# M103.net
KiCad netlist of a schematic drawn in EAGLE
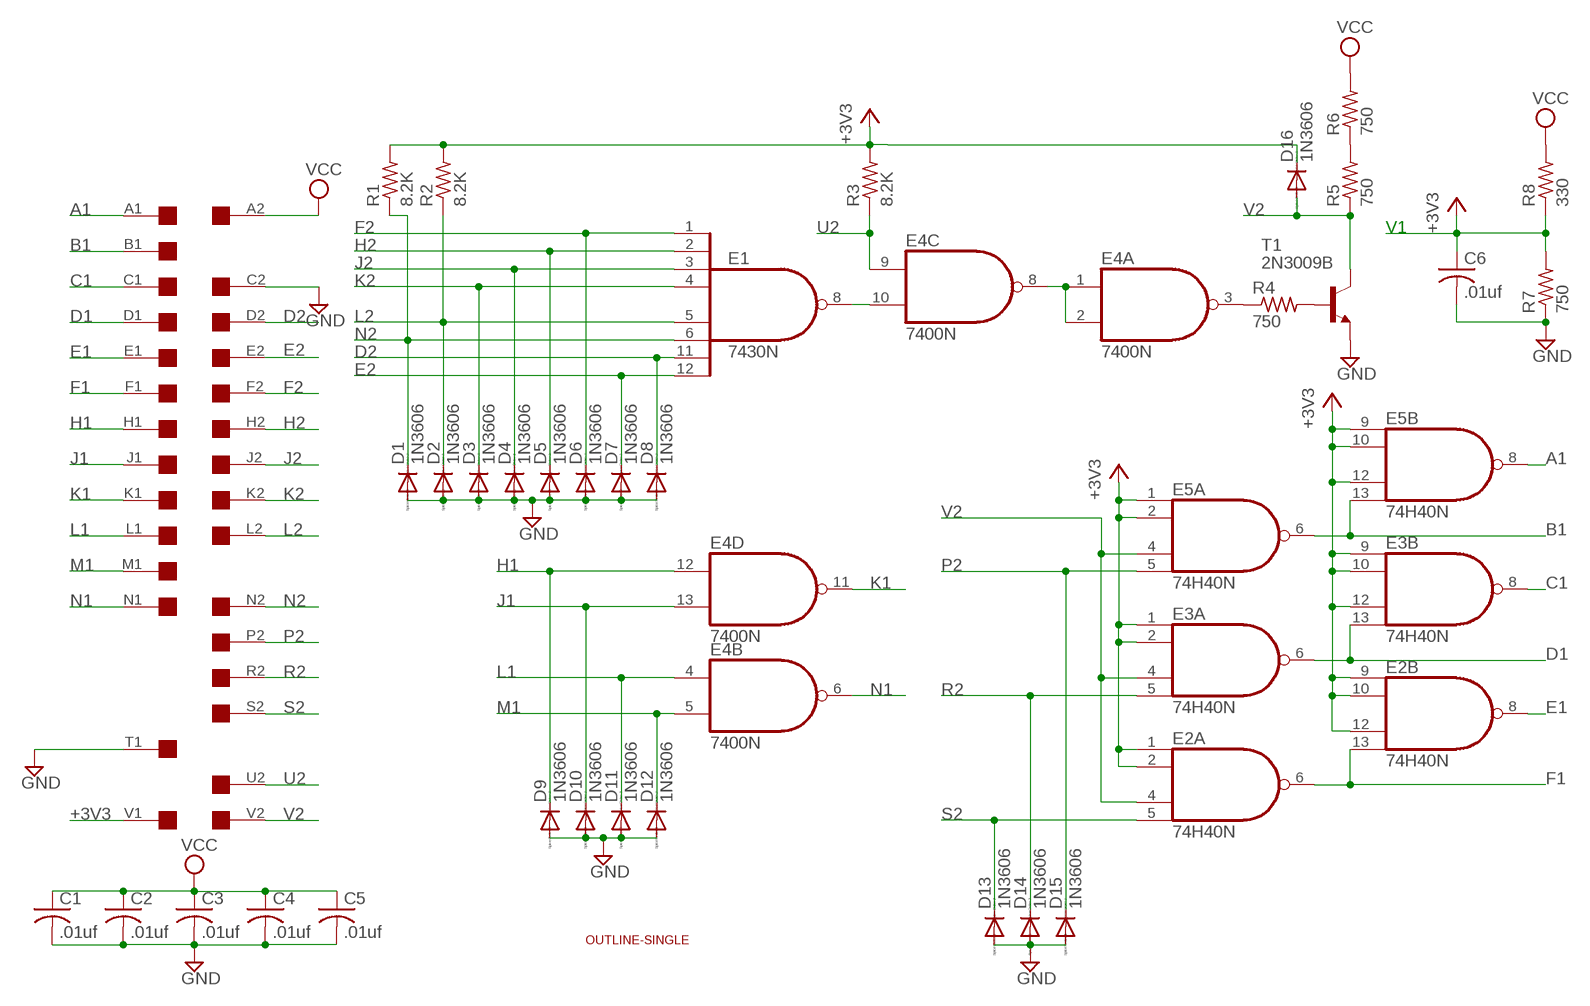
[diagram p0: schematic, sheet 1]

(export (version "E")
  (design (tool "Eeschema 10.0.6"))
  (components
    (comp (ref "C1")
      (value ".01uf")
      (footprint "eagle-import:C050-025X075")
      (libsource (lib "eagle-import") (part "C-US050-025X075"))
    )
    (comp (ref "C2")
      (value ".01uf")
      (footprint "eagle-import:C050-025X075")
      (libsource (lib "eagle-import") (part "C-US050-025X075"))
    )
    (comp (ref "C3")
      (value ".01uf")
      (footprint "eagle-import:C050-025X075")
      (libsource (lib "eagle-import") (part "C-US050-025X075"))
    )
    (comp (ref "C4")
      (value ".01uf")
      (footprint "eagle-import:C050-025X075")
      (libsource (lib "eagle-import") (part "C-US050-025X075"))
    )
    (comp (ref "C5")
      (value ".01uf")
      (footprint "eagle-import:C050-025X075")
      (libsource (lib "eagle-import") (part "C-US050-025X075"))
    )
    (comp (ref "C6")
      (value ".01uf")
      (footprint "eagle-import:C050-025X075")
      (libsource (lib "eagle-import") (part "C-US050-025X075"))
    )
    (comp (ref "D1")
      (value "1N3606")
      (footprint "eagle-import:DO35-10")
      (libsource (lib "eagle-import") (part "1N4148DO35-10"))
    )
    (comp (ref "D2")
      (value "1N3606")
      (footprint "eagle-import:DO35-10")
      (libsource (lib "eagle-import") (part "1N4148DO35-10"))
    )
    (comp (ref "D3")
      (value "1N3606")
      (footprint "eagle-import:DO35-10")
      (libsource (lib "eagle-import") (part "1N4148DO35-10"))
    )
    (comp (ref "D4")
      (value "1N3606")
      (footprint "eagle-import:DO35-10")
      (libsource (lib "eagle-import") (part "1N4148DO35-10"))
    )
    (comp (ref "D5")
      (value "1N3606")
      (footprint "eagle-import:DO35-10")
      (libsource (lib "eagle-import") (part "1N4148DO35-10"))
    )
    (comp (ref "D6")
      (value "1N3606")
      (footprint "eagle-import:DO35-10")
      (libsource (lib "eagle-import") (part "1N4148DO35-10"))
    )
    (comp (ref "D7")
      (value "1N3606")
      (footprint "eagle-import:DO35-10")
      (libsource (lib "eagle-import") (part "1N4148DO35-10"))
    )
    (comp (ref "D8")
      (value "1N3606")
      (footprint "eagle-import:DO35-10")
      (libsource (lib "eagle-import") (part "1N4148DO35-10"))
    )
    (comp (ref "D9")
      (value "1N3606")
      (footprint "eagle-import:DO35-10")
      (libsource (lib "eagle-import") (part "1N4148DO35-10"))
    )
    (comp (ref "D10")
      (value "1N3606")
      (footprint "eagle-import:DO35-10")
      (libsource (lib "eagle-import") (part "1N4148DO35-10"))
    )
    (comp (ref "D11")
      (value "1N3606")
      (footprint "eagle-import:DO35-10")
      (libsource (lib "eagle-import") (part "1N4148DO35-10"))
    )
    (comp (ref "D12")
      (value "1N3606")
      (footprint "eagle-import:DO35-10")
      (libsource (lib "eagle-import") (part "1N4148DO35-10"))
    )
    (comp (ref "D13")
      (value "1N3606")
      (footprint "eagle-import:DO35-10")
      (libsource (lib "eagle-import") (part "1N4148DO35-10"))
    )
    (comp (ref "D14")
      (value "1N3606")
      (footprint "eagle-import:DO35-10")
      (libsource (lib "eagle-import") (part "1N4148DO35-10"))
    )
    (comp (ref "D15")
      (value "1N3606")
      (footprint "eagle-import:DO35-10")
      (libsource (lib "eagle-import") (part "1N4148DO35-10"))
    )
    (comp (ref "D16")
      (value "1N3606")
      (footprint "eagle-import:DO35-10")
      (libsource (lib "eagle-import") (part "1N4148DO35-10"))
    )
    (comp (ref "E1")
      (value "7430N")
      (footprint "eagle-import:DIL14")
      (libsource (lib "eagle-import") (part "7430N"))
    )
    (comp (ref "E2")
      (value "74H40N")
      (footprint "eagle-import:DIL14")
      (libsource (lib "eagle-import") (part "7420NS"))
    )
    (comp (ref "E3")
      (value "74H40N")
      (footprint "eagle-import:DIL14")
      (libsource (lib "eagle-import") (part "7420NS"))
    )
    (comp (ref "E4")
      (value "7400N")
      (footprint "eagle-import:DIL14")
      (libsource (lib "eagle-import") (part "7400N"))
    )
    (comp (ref "E5")
      (value "74H40N")
      (footprint "eagle-import:DIL14")
      (libsource (lib "eagle-import") (part "7420NS"))
    )
    (comp (ref "R1")
      (value "8.2K")
      (footprint "eagle-import:0207_10")
      (libsource (lib "eagle-import") (part "R-US_0207/10"))
    )
    (comp (ref "R2")
      (value "8.2K")
      (footprint "eagle-import:0207_10")
      (libsource (lib "eagle-import") (part "R-US_0207/10"))
    )
    (comp (ref "R3")
      (value "8.2K")
      (footprint "eagle-import:0207_10")
      (libsource (lib "eagle-import") (part "R-US_0207/10"))
    )
    (comp (ref "R4")
      (value "750")
      (footprint "eagle-import:0207_10")
      (libsource (lib "eagle-import") (part "R-US_0207/10"))
    )
    (comp (ref "R5")
      (value "750")
      (footprint "eagle-import:0207_10")
      (libsource (lib "eagle-import") (part "R-US_0207/10"))
    )
    (comp (ref "R6")
      (value "750")
      (footprint "eagle-import:0207_10")
      (libsource (lib "eagle-import") (part "R-US_0207/10"))
    )
    (comp (ref "R7")
      (value "750")
      (footprint "eagle-import:0207_10")
      (libsource (lib "eagle-import") (part "R-US_0207/10"))
    )
    (comp (ref "R8")
      (value "330")
      (footprint "eagle-import:0207_10")
      (libsource (lib "eagle-import") (part "R-US_0207/10"))
    )
    (comp (ref "T1")
      (value "2N3009B")
      (footprint "eagle-import:TO39")
      (libsource (lib "eagle-import") (part "-NPN-TO39-EBC2N1613"))
    )
    (comp (ref "U$8")
      (value "SINGLE")
      (footprint "eagle-import:EDGE-CON2")
      (libsource (lib "eagle-import") (part "SINGLE"))
    )
    (comp (ref "U$9")
      (value "OUTLINE-SINGLE")
      (footprint "eagle-import:SINGLE")
      (libsource (lib "eagle-import") (part "OUTLINE-SINGLE"))
    )
  )
  (nets
    (net (code "1") (name "+3V3") (class "Default")
      (node (ref "C6") (pin "1") (pinfunction "1_1") (pintype "passive"))
      (node (ref "D16") (pin "C") (pinfunction "C_C") (pintype "passive"))
      (node (ref "E2") (pin "1") (pinfunction "I0_1") (pintype "input"))
      (node (ref "E2") (pin "10") (pinfunction "I1_10") (pintype "input"))
      (node (ref "E2") (pin "12") (pinfunction "I2_12") (pintype "input"))
      (node (ref "E2") (pin "2") (pinfunction "I1_2") (pintype "input"))
      (node (ref "E2") (pin "9") (pinfunction "I0_9") (pintype "input"))
      (node (ref "E3") (pin "1") (pinfunction "I0_1") (pintype "input"))
      (node (ref "E3") (pin "10") (pinfunction "I1_10") (pintype "input"))
      (node (ref "E3") (pin "12") (pinfunction "I2_12") (pintype "input"))
      (node (ref "E3") (pin "2") (pinfunction "I1_2") (pintype "input"))
      (node (ref "E3") (pin "9") (pinfunction "I0_9") (pintype "input"))
      (node (ref "E5") (pin "1") (pinfunction "I0_1") (pintype "input"))
      (node (ref "E5") (pin "10") (pinfunction "I1_10") (pintype "input"))
      (node (ref "E5") (pin "12") (pinfunction "I2_12") (pintype "input"))
      (node (ref "E5") (pin "2") (pinfunction "I1_2") (pintype "input"))
      (node (ref "E5") (pin "9") (pinfunction "I0_9") (pintype "input"))
      (node (ref "R1") (pin "2") (pinfunction "2_2") (pintype "passive"))
      (node (ref "R2") (pin "2") (pinfunction "2_2") (pintype "passive"))
      (node (ref "R3") (pin "2") (pinfunction "2_2") (pintype "passive"))
      (node (ref "R7") (pin "2") (pinfunction "2_2") (pintype "passive"))
      (node (ref "R8") (pin "1") (pinfunction "1_1") (pintype "passive"))
      (node (ref "U$8") (pin "V1") (pinfunction "1_V1") (pintype "bidirectional"))
    )
    (net (code "2") (name "/A1") (class "Default")
      (node (ref "E5") (pin "8") (pinfunction "O_8") (pintype "output"))
      (node (ref "U$8") (pin "A1") (pinfunction "1_A1") (pintype "bidirectional"))
    )
    (net (code "3") (name "/B1") (class "Default")
      (node (ref "E5") (pin "13") (pinfunction "I3_13") (pintype "input"))
      (node (ref "E5") (pin "6") (pinfunction "O_6") (pintype "output"))
      (node (ref "U$8") (pin "B1") (pinfunction "1_B1") (pintype "bidirectional"))
    )
    (net (code "4") (name "/C1") (class "Default")
      (node (ref "E3") (pin "8") (pinfunction "O_8") (pintype "output"))
      (node (ref "U$8") (pin "C1") (pinfunction "1_C1") (pintype "bidirectional"))
    )
    (net (code "5") (name "/D1") (class "Default")
      (node (ref "E3") (pin "13") (pinfunction "I3_13") (pintype "input"))
      (node (ref "E3") (pin "6") (pinfunction "O_6") (pintype "output"))
      (node (ref "U$8") (pin "D1") (pinfunction "1_D1") (pintype "bidirectional"))
    )
    (net (code "6") (name "/D2") (class "Default")
      (node (ref "D8") (pin "C") (pinfunction "C_C") (pintype "passive"))
      (node (ref "E1") (pin "11") (pinfunction "I6_11") (pintype "input"))
      (node (ref "U$8") (pin "D2") (pinfunction "1_D2") (pintype "bidirectional"))
    )
    (net (code "7") (name "/E1") (class "Default")
      (node (ref "E2") (pin "8") (pinfunction "O_8") (pintype "output"))
      (node (ref "U$8") (pin "E1") (pinfunction "1_E1") (pintype "bidirectional"))
    )
    (net (code "8") (name "/E2") (class "Default")
      (node (ref "D7") (pin "C") (pinfunction "C_C") (pintype "passive"))
      (node (ref "E1") (pin "12") (pinfunction "I7_12") (pintype "input"))
      (node (ref "U$8") (pin "E2") (pinfunction "1_E2") (pintype "bidirectional"))
    )
    (net (code "9") (name "/F1") (class "Default")
      (node (ref "E2") (pin "13") (pinfunction "I3_13") (pintype "input"))
      (node (ref "E2") (pin "6") (pinfunction "O_6") (pintype "output"))
      (node (ref "U$8") (pin "F1") (pinfunction "1_F1") (pintype "bidirectional"))
    )
    (net (code "10") (name "/F2") (class "Default")
      (node (ref "D6") (pin "C") (pinfunction "C_C") (pintype "passive"))
      (node (ref "E1") (pin "1") (pinfunction "I0_1") (pintype "input"))
      (node (ref "U$8") (pin "F2") (pinfunction "1_F2") (pintype "bidirectional"))
    )
    (net (code "11") (name "/H1") (class "Default")
      (node (ref "D9") (pin "C") (pinfunction "C_C") (pintype "passive"))
      (node (ref "E4") (pin "12") (pinfunction "I0_12") (pintype "input"))
      (node (ref "U$8") (pin "H1") (pinfunction "1_H1") (pintype "bidirectional"))
    )
    (net (code "12") (name "/H2") (class "Default")
      (node (ref "D5") (pin "C") (pinfunction "C_C") (pintype "passive"))
      (node (ref "E1") (pin "2") (pinfunction "I1_2") (pintype "input"))
      (node (ref "U$8") (pin "H2") (pinfunction "1_H2") (pintype "bidirectional"))
    )
    (net (code "13") (name "/J1") (class "Default")
      (node (ref "D10") (pin "C") (pinfunction "C_C") (pintype "passive"))
      (node (ref "E4") (pin "13") (pinfunction "I1_13") (pintype "input"))
      (node (ref "U$8") (pin "J1") (pinfunction "1_J1") (pintype "bidirectional"))
    )
    (net (code "14") (name "/J2") (class "Default")
      (node (ref "D4") (pin "C") (pinfunction "C_C") (pintype "passive"))
      (node (ref "E1") (pin "3") (pinfunction "I2_3") (pintype "input"))
      (node (ref "U$8") (pin "J2") (pinfunction "1_J2") (pintype "bidirectional"))
    )
    (net (code "15") (name "/K1") (class "Default")
      (node (ref "E4") (pin "11") (pinfunction "O_11") (pintype "output"))
      (node (ref "U$8") (pin "K1") (pinfunction "1_K1") (pintype "bidirectional"))
    )
    (net (code "16") (name "/K2") (class "Default")
      (node (ref "D3") (pin "C") (pinfunction "C_C") (pintype "passive"))
      (node (ref "E1") (pin "4") (pinfunction "I3_4") (pintype "input"))
      (node (ref "U$8") (pin "K2") (pinfunction "1_K2") (pintype "bidirectional"))
    )
    (net (code "17") (name "/L1") (class "Default")
      (node (ref "D11") (pin "C") (pinfunction "C_C") (pintype "passive"))
      (node (ref "E4") (pin "4") (pinfunction "I0_4") (pintype "input"))
      (node (ref "U$8") (pin "L1") (pinfunction "1_L1") (pintype "bidirectional"))
    )
    (net (code "18") (name "/L2") (class "Default")
      (node (ref "D2") (pin "C") (pinfunction "C_C") (pintype "passive"))
      (node (ref "E1") (pin "5") (pinfunction "I4_5") (pintype "input"))
      (node (ref "R2") (pin "1") (pinfunction "1_1") (pintype "passive"))
      (node (ref "U$8") (pin "L2") (pinfunction "1_L2") (pintype "bidirectional"))
    )
    (net (code "19") (name "/M1") (class "Default")
      (node (ref "D12") (pin "C") (pinfunction "C_C") (pintype "passive"))
      (node (ref "E4") (pin "5") (pinfunction "I1_5") (pintype "input"))
      (node (ref "U$8") (pin "M1") (pinfunction "1_M1") (pintype "bidirectional"))
    )
    (net (code "20") (name "/N1") (class "Default")
      (node (ref "E4") (pin "6") (pinfunction "O_6") (pintype "output"))
      (node (ref "U$8") (pin "N1") (pinfunction "1_N1") (pintype "bidirectional"))
    )
    (net (code "21") (name "/N2") (class "Default")
      (node (ref "D1") (pin "C") (pinfunction "C_C") (pintype "passive"))
      (node (ref "E1") (pin "6") (pinfunction "I5_6") (pintype "input"))
      (node (ref "R1") (pin "1") (pinfunction "1_1") (pintype "passive"))
      (node (ref "U$8") (pin "N2") (pinfunction "1_N2") (pintype "bidirectional"))
    )
    (net (code "22") (name "/P2") (class "Default")
      (node (ref "D15") (pin "C") (pinfunction "C_C") (pintype "passive"))
      (node (ref "E5") (pin "5") (pinfunction "I3_5") (pintype "input"))
      (node (ref "U$8") (pin "P2") (pinfunction "1_P2") (pintype "bidirectional"))
    )
    (net (code "23") (name "/R2") (class "Default")
      (node (ref "D14") (pin "C") (pinfunction "C_C") (pintype "passive"))
      (node (ref "E3") (pin "5") (pinfunction "I3_5") (pintype "input"))
      (node (ref "U$8") (pin "R2") (pinfunction "1_R2") (pintype "bidirectional"))
    )
    (net (code "24") (name "/S2") (class "Default")
      (node (ref "D13") (pin "C") (pinfunction "C_C") (pintype "passive"))
      (node (ref "E2") (pin "5") (pinfunction "I3_5") (pintype "input"))
      (node (ref "U$8") (pin "S2") (pinfunction "1_S2") (pintype "bidirectional"))
    )
    (net (code "25") (name "/U2") (class "Default")
      (node (ref "E4") (pin "9") (pinfunction "I0_9") (pintype "input"))
      (node (ref "R3") (pin "1") (pinfunction "1_1") (pintype "passive"))
      (node (ref "U$8") (pin "U2") (pinfunction "1_U2") (pintype "bidirectional"))
    )
    (net (code "26") (name "/V2") (class "Default")
      (node (ref "D16") (pin "A") (pinfunction "A_A") (pintype "passive"))
      (node (ref "E2") (pin "4") (pinfunction "I2_4") (pintype "input"))
      (node (ref "E3") (pin "4") (pinfunction "I2_4") (pintype "input"))
      (node (ref "E5") (pin "4") (pinfunction "I2_4") (pintype "input"))
      (node (ref "R5") (pin "1") (pinfunction "1_1") (pintype "passive"))
      (node (ref "T1") (pin "3") (pinfunction "C_3") (pintype "passive"))
      (node (ref "U$8") (pin "V2") (pinfunction "1_V2") (pintype "bidirectional"))
    )
    (net (code "27") (name "GND") (class "Default")
      (node (ref "C1") (pin "2") (pinfunction "2_2") (pintype "passive"))
      (node (ref "C2") (pin "2") (pinfunction "2_2") (pintype "passive"))
      (node (ref "C3") (pin "2") (pinfunction "2_2") (pintype "passive"))
      (node (ref "C4") (pin "2") (pinfunction "2_2") (pintype "passive"))
      (node (ref "C5") (pin "2") (pinfunction "2_2") (pintype "passive"))
      (node (ref "C6") (pin "2") (pinfunction "2_2") (pintype "passive"))
      (node (ref "D1") (pin "A") (pinfunction "A_A") (pintype "passive"))
      (node (ref "D10") (pin "A") (pinfunction "A_A") (pintype "passive"))
      (node (ref "D11") (pin "A") (pinfunction "A_A") (pintype "passive"))
      (node (ref "D12") (pin "A") (pinfunction "A_A") (pintype "passive"))
      (node (ref "D13") (pin "A") (pinfunction "A_A") (pintype "passive"))
      (node (ref "D14") (pin "A") (pinfunction "A_A") (pintype "passive"))
      (node (ref "D15") (pin "A") (pinfunction "A_A") (pintype "passive"))
      (node (ref "D2") (pin "A") (pinfunction "A_A") (pintype "passive"))
      (node (ref "D3") (pin "A") (pinfunction "A_A") (pintype "passive"))
      (node (ref "D4") (pin "A") (pinfunction "A_A") (pintype "passive"))
      (node (ref "D5") (pin "A") (pinfunction "A_A") (pintype "passive"))
      (node (ref "D6") (pin "A") (pinfunction "A_A") (pintype "passive"))
      (node (ref "D7") (pin "A") (pinfunction "A_A") (pintype "passive"))
      (node (ref "D8") (pin "A") (pinfunction "A_A") (pintype "passive"))
      (node (ref "D9") (pin "A") (pinfunction "A_A") (pintype "passive"))
      (node (ref "R7") (pin "1") (pinfunction "1_1") (pintype "passive"))
      (node (ref "T1") (pin "1") (pinfunction "E_1") (pintype "passive"))
      (node (ref "U$8") (pin "C2") (pinfunction "1_C2") (pintype "bidirectional"))
      (node (ref "U$8") (pin "T1") (pinfunction "1_T1") (pintype "bidirectional"))
    )
    (net (code "28") (name "Net-(E1A-O)") (class "Default")
      (node (ref "E1") (pin "8") (pinfunction "O_8") (pintype "output"))
      (node (ref "E4") (pin "10") (pinfunction "I1_10") (pintype "input"))
    )
    (net (code "29") (name "Net-(E4A-I0)") (class "Default")
      (node (ref "E4") (pin "1") (pinfunction "I0_1") (pintype "input"))
      (node (ref "E4") (pin "2") (pinfunction "I1_2") (pintype "input"))
      (node (ref "E4") (pin "8") (pinfunction "O_8") (pintype "output"))
    )
    (net (code "30") (name "Net-(E4A-O)") (class "Default")
      (node (ref "E4") (pin "3") (pinfunction "O_3") (pintype "output"))
      (node (ref "R4") (pin "1") (pinfunction "1_1") (pintype "passive"))
    )
    (net (code "31") (name "Net-(R5-Pad2)") (class "Default")
      (node (ref "R5") (pin "2") (pinfunction "2_2") (pintype "passive"))
      (node (ref "R6") (pin "1") (pinfunction "1_1") (pintype "passive"))
    )
    (net (code "32") (name "Net-(T1-B)") (class "Default")
      (node (ref "R4") (pin "2") (pinfunction "2_2") (pintype "passive"))
      (node (ref "T1") (pin "2") (pinfunction "B_2") (pintype "passive"))
    )
    (net (code "33") (name "VCC") (class "Default")
      (node (ref "C1") (pin "1") (pinfunction "1_1") (pintype "passive"))
      (node (ref "C2") (pin "1") (pinfunction "1_1") (pintype "passive"))
      (node (ref "C3") (pin "1") (pinfunction "1_1") (pintype "passive"))
      (node (ref "C4") (pin "1") (pinfunction "1_1") (pintype "passive"))
      (node (ref "C5") (pin "1") (pinfunction "1_1") (pintype "passive"))
      (node (ref "R6") (pin "2") (pinfunction "2_2") (pintype "passive"))
      (node (ref "R8") (pin "2") (pinfunction "2_2") (pintype "passive"))
      (node (ref "U$8") (pin "A2") (pinfunction "1_A2") (pintype "bidirectional"))
    )
  )
)
